# 03-PeripheralPart-V2_2.net
KiCad netlist of a schematic drawn in Altium Designer
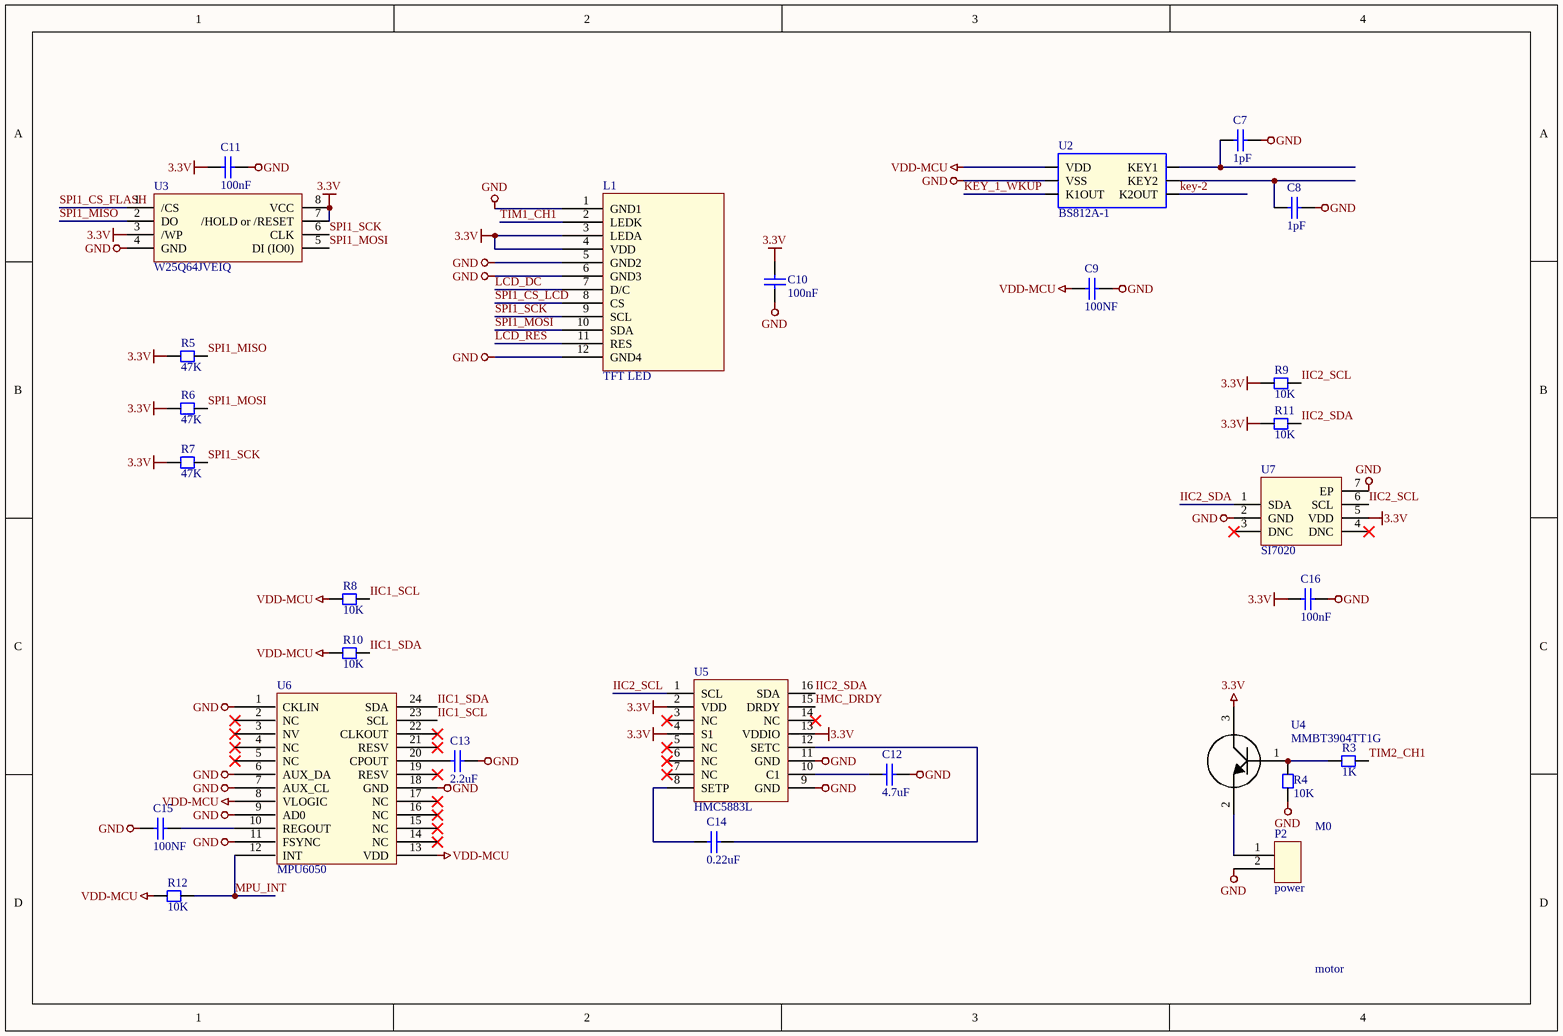
[diagram p0: 03-PeripheralPart-V2.2.SchDoc]

(export (version "E")
  (design (tool "Eeschema 10.0.6"))
  (components
    (comp (ref "C7")
      (value "1pF")
      (footprint "CC1005-0402")
      (description "贴片电容")
      (libsource (lib "tianxiaohua_Schlib") (part "Chip capacitor"))
    )
    (comp (ref "C8")
      (value "1pF")
      (footprint "CC1005-0402")
      (description "贴片电容")
      (libsource (lib "tianxiaohua_Schlib") (part "Chip capacitor"))
    )
    (comp (ref "C9")
      (value "100NF")
      (footprint "CC1005-0402")
      (description "贴片电容")
      (libsource (lib "tianxiaohua_Schlib") (part "Chip capacitor"))
    )
    (comp (ref "C10")
      (value "100nF")
      (footprint "CC1005-0402")
      (description "贴片电容")
      (libsource (lib "tianxiaohua_Schlib") (part "Chip capacitor"))
    )
    (comp (ref "C11")
      (value "100nF")
      (footprint "CC1005-0402")
      (description "贴片电容")
      (libsource (lib "tianxiaohua_Schlib") (part "Chip capacitor"))
    )
    (comp (ref "C12")
      (value "4.7uF")
      (footprint "CC1005-0402")
      (description "贴片电容")
      (libsource (lib "tianxiaohua_Schlib") (part "Chip capacitor"))
    )
    (comp (ref "C13")
      (value "2.2uF")
      (footprint "CC1005-0402")
      (description "贴片电容")
      (libsource (lib "tianxiaohua_Schlib") (part "Chip capacitor"))
    )
    (comp (ref "C14")
      (value "0.22uF")
      (footprint "CC1005-0402")
      (description "贴片电容")
      (libsource (lib "tianxiaohua_Schlib") (part "Chip capacitor"))
    )
    (comp (ref "C15")
      (value "100NF")
      (footprint "CC1005-0402")
      (description "贴片电容")
      (libsource (lib "tianxiaohua_Schlib") (part "Chip capacitor"))
    )
    (comp (ref "C16")
      (value "100nF")
      (footprint "CC1005-0402")
      (description "贴片电容")
      (libsource (lib "tianxiaohua_Schlib") (part "Chip capacitor"))
    )
    (comp (ref "L1")
      (value "TFT LED")
      (footprint "LCD-1.3-(2)")
      (description "1.3寸显示屏幕")
      (libsource (lib "tianxiaohua_Schlib") (part "LCD-IPSscreen-1.3"))
    )
    (comp (ref "M0")
      (value "motor")
      (footprint "motor")
      (description "震动马达")
      (libsource (lib "tianxiaohua_Schlib") (part "motor"))
    )
    (comp (ref "P2")
      (value "power")
      (footprint "POWER-3.7V")
      (libsource (lib "tianxiaohua_Schlib") (part "power"))
    )
    (comp (ref "R3")
      (value "1K")
      (footprint "CR1005-0402")
      (description "贴片电阻")
      (libsource (lib "tianxiaohua_Schlib") (part "Chip resistor"))
    )
    (comp (ref "R4")
      (value "10K")
      (footprint "CR1005-0402")
      (description "贴片电阻")
      (libsource (lib "") (part "Chip resistor_1"))
    )
    (comp (ref "R5")
      (value "47K")
      (footprint "CR1005-0402")
      (description "贴片电阻")
      (libsource (lib "tianxiaohua_Schlib") (part "Chip resistor"))
    )
    (comp (ref "R6")
      (value "47K")
      (footprint "CR1005-0402")
      (description "贴片电阻")
      (libsource (lib "tianxiaohua_Schlib") (part "Chip resistor"))
    )
    (comp (ref "R7")
      (value "47K")
      (footprint "CR1005-0402")
      (description "贴片电阻")
      (libsource (lib "tianxiaohua_Schlib") (part "Chip resistor"))
    )
    (comp (ref "R8")
      (value "10K")
      (footprint "CR1005-0402")
      (description "贴片电阻")
      (libsource (lib "tianxiaohua_Schlib") (part "Chip resistor"))
    )
    (comp (ref "R9")
      (value "10K")
      (footprint "CR1005-0402")
      (description "贴片电阻")
      (libsource (lib "tianxiaohua_Schlib") (part "Chip resistor"))
    )
    (comp (ref "R10")
      (value "10K")
      (footprint "CR1005-0402")
      (description "贴片电阻")
      (libsource (lib "tianxiaohua_Schlib") (part "Chip resistor"))
    )
    (comp (ref "R11")
      (value "10K")
      (footprint "CR1005-0402")
      (description "贴片电阻")
      (libsource (lib "tianxiaohua_Schlib") (part "Chip resistor"))
    )
    (comp (ref "R12")
      (value "10K")
      (footprint "CR1005-0402")
      (description "贴片电阻")
      (libsource (lib "tianxiaohua_Schlib") (part "Chip resistor"))
    )
    (comp (ref "U2")
      (value "BS812A-1")
      (footprint "SOT23-6")
      (description "触摸按键 两路 SOP23-6封装极简电路")
      (libsource (lib "tianxiaohua_Schlib") (part "BS812A-1"))
    )
    (comp (ref "U3")
      (value "W25Q64JVEIQ")
      (footprint "WSON-8_L8.0-W6.10-P1.27-TL-EP")
      (description "FLASH")
      (libsource (lib "tianxiaohua_Schlib") (part "W25Q256JVEIQ"))
    )
    (comp (ref "U4")
      (value "MMBT3904TT1G")
      (footprint "SOT-416")
      (description "NPN 电流 - 集电极（Ic）（最大值）：200mA 电压 - 集射极击穿（最大值）：40V SOT-23-3")
      (libsource (lib "tianxiaohua_Schlib") (part "MMBT3904TT1G"))
    )
    (comp (ref "U5")
      (value "HMC5883L")
      (footprint "LPCC-16_L3.0-W3.0-P0.50-BL")
      (description "三轴罗盘")
      (libsource (lib "tianxiaohua_Schlib") (part "HMC5883L"))
    )
    (comp (ref "U6")
      (value "MPU6050")
      (footprint "QFN24 - duplicate")
      (description "陀螺仪")
      (libsource (lib "tianxiaohua_Schlib") (part "MPU6050"))
    )
    (comp (ref "U7")
      (value "SI7020")
      (footprint "DFN-6")
      (description "温湿度传感器芯片")
      (libsource (lib "tianxiaohua_Schlib") (part "SI7020"))
    )
  )
  (nets
    (net (code "1") (name "/HMC_DRDY") (class "Default")
      (node (ref "U5") (pin "15") (pinfunction "DRDY_15") (pintype "passive"))
    )
    (net (code "2") (name "/IIC1_SCL") (class "Default")
      (node (ref "R8") (pin "1") (pinfunction "1_1") (pintype "passive"))
      (node (ref "U6") (pin "23") (pinfunction "SCL_23") (pintype "passive"))
    )
    (net (code "3") (name "/IIC1_SDA") (class "Default")
      (node (ref "R10") (pin "1") (pinfunction "1_1") (pintype "passive"))
      (node (ref "U6") (pin "24") (pinfunction "SDA_24") (pintype "passive"))
    )
    (net (code "4") (name "/IIC2_SCL") (class "Default")
      (node (ref "R9") (pin "1") (pinfunction "1_1") (pintype "passive"))
      (node (ref "U5") (pin "1") (pinfunction "SCL_1") (pintype "passive"))
      (node (ref "U7") (pin "6") (pinfunction "SCL_6") (pintype "passive"))
    )
    (net (code "5") (name "/IIC2_SDA") (class "Default")
      (node (ref "R11") (pin "1") (pinfunction "1_1") (pintype "passive"))
      (node (ref "U5") (pin "16") (pinfunction "SDA_16") (pintype "passive"))
      (node (ref "U7") (pin "1") (pinfunction "SDA_1") (pintype "passive"))
    )
    (net (code "6") (name "/KEY_1_WKUP") (class "Default")
      (node (ref "U2") (pin "3") (pinfunction "K1OUT_3") (pintype "passive"))
    )
    (net (code "7") (name "/LCD_DC") (class "Default")
      (node (ref "L1") (pin "7") (pinfunction "D/C_7") (pintype "passive"))
    )
    (net (code "8") (name "/LCD_RES") (class "Default")
      (node (ref "L1") (pin "11") (pinfunction "RES_11") (pintype "passive"))
    )
    (net (code "9") (name "/MPU_INT") (class "Default")
      (node (ref "R12") (pin "1") (pinfunction "1_1") (pintype "passive"))
      (node (ref "U6") (pin "12") (pinfunction "INT_12") (pintype "passive"))
    )
    (net (code "10") (name "/SPI1_CS_FLASH") (class "Default")
      (node (ref "U3") (pin "1") (pinfunction "/CS_1") (pintype "passive"))
    )
    (net (code "11") (name "/SPI1_CS_LCD") (class "Default")
      (node (ref "L1") (pin "8") (pinfunction "CS_8") (pintype "passive"))
    )
    (net (code "12") (name "/SPI1_MISO") (class "Default")
      (node (ref "R5") (pin "1") (pinfunction "1_1") (pintype "passive"))
      (node (ref "U3") (pin "2") (pinfunction "DO_2") (pintype "passive"))
    )
    (net (code "13") (name "/SPI1_MOSI") (class "Default")
      (node (ref "L1") (pin "10") (pinfunction "SDA_10") (pintype "passive"))
      (node (ref "R6") (pin "1") (pinfunction "1_1") (pintype "passive"))
      (node (ref "U3") (pin "5") (pinfunction "DI_(IO0)_5") (pintype "passive"))
    )
    (net (code "14") (name "/SPI1_SCK") (class "Default")
      (node (ref "L1") (pin "9") (pinfunction "SCL_9") (pintype "passive"))
      (node (ref "R7") (pin "1") (pinfunction "1_1") (pintype "passive"))
      (node (ref "U3") (pin "6") (pinfunction "CLK_6") (pintype "passive"))
    )
    (net (code "15") (name "/TIM1_CH1") (class "Default")
      (node (ref "L1") (pin "2") (pinfunction "LEDK_2") (pintype "passive"))
    )
    (net (code "16") (name "/TIM2_CH1") (class "Default")
      (node (ref "R3") (pin "1") (pinfunction "1_1") (pintype "passive"))
    )
    (net (code "17") (name "/key-2") (class "Default")
      (node (ref "U2") (pin "4") (pinfunction "K2OUT_4") (pintype "passive"))
    )
    (net (code "18") (name "3.3V") (class "Default")
      (node (ref "C10") (pin "1") (pinfunction "1_1") (pintype "passive"))
      (node (ref "C11") (pin "1") (pinfunction "1_1") (pintype "passive"))
      (node (ref "C16") (pin "1") (pinfunction "1_1") (pintype "passive"))
      (node (ref "L1") (pin "3") (pinfunction "LEDA_3") (pintype "passive"))
      (node (ref "L1") (pin "4") (pinfunction "VDD_4") (pintype "passive"))
      (node (ref "R11") (pin "2") (pinfunction "2_2") (pintype "passive"))
      (node (ref "R5") (pin "2") (pinfunction "2_2") (pintype "passive"))
      (node (ref "R6") (pin "2") (pinfunction "2_2") (pintype "passive"))
      (node (ref "R7") (pin "2") (pinfunction "2_2") (pintype "passive"))
      (node (ref "R9") (pin "2") (pinfunction "2_2") (pintype "passive"))
      (node (ref "U3") (pin "3") (pinfunction "/WP_3") (pintype "passive"))
      (node (ref "U3") (pin "7") (pinfunction "/HOLD_or_/RESET_7") (pintype "passive"))
      (node (ref "U3") (pin "8") (pinfunction "VCC_8") (pintype "passive"))
      (node (ref "U4") (pin "3") (pinfunction "3_3") (pintype "passive"))
      (node (ref "U5") (pin "13") (pinfunction "VDDIO_13") (pintype "passive"))
      (node (ref "U5") (pin "2") (pinfunction "VDD_2") (pintype "passive"))
      (node (ref "U5") (pin "4") (pinfunction "S1_4") (pintype "passive"))
      (node (ref "U7") (pin "5") (pinfunction "VDD_5") (pintype "passive"))
    )
    (net (code "19") (name "GND") (class "Default")
      (node (ref "C10") (pin "2") (pinfunction "2_2") (pintype "passive"))
      (node (ref "C11") (pin "2") (pinfunction "2_2") (pintype "passive"))
      (node (ref "C12") (pin "2") (pinfunction "2_2") (pintype "passive"))
      (node (ref "C13") (pin "2") (pinfunction "2_2") (pintype "passive"))
      (node (ref "C15") (pin "1") (pinfunction "1_1") (pintype "passive"))
      (node (ref "C16") (pin "2") (pinfunction "2_2") (pintype "passive"))
      (node (ref "C7") (pin "2") (pinfunction "2_2") (pintype "passive"))
      (node (ref "C8") (pin "2") (pinfunction "2_2") (pintype "passive"))
      (node (ref "C9") (pin "1") (pinfunction "1_1") (pintype "passive"))
      (node (ref "L1") (pin "1") (pinfunction "GND1_1") (pintype "passive"))
      (node (ref "L1") (pin "12") (pinfunction "GND4_12") (pintype "passive"))
      (node (ref "L1") (pin "5") (pinfunction "GND2_5") (pintype "passive"))
      (node (ref "L1") (pin "6") (pinfunction "GND3_6") (pintype "passive"))
      (node (ref "P2") (pin "2") (pinfunction "2_2") (pintype "passive"))
      (node (ref "R4") (pin "2") (pinfunction "2_2") (pintype "passive"))
      (node (ref "U2") (pin "2") (pinfunction "VSS_2") (pintype "passive"))
      (node (ref "U3") (pin "4") (pinfunction "GND_4") (pintype "passive"))
      (node (ref "U5") (pin "11") (pinfunction "GND_11") (pintype "passive"))
      (node (ref "U5") (pin "9") (pinfunction "GND_9") (pintype "passive"))
      (node (ref "U6") (pin "1") (pinfunction "CKLIN_1") (pintype "passive"))
      (node (ref "U6") (pin "11") (pinfunction "FSYNC_11") (pintype "passive"))
      (node (ref "U6") (pin "18") (pinfunction "GND_18") (pintype "passive"))
      (node (ref "U6") (pin "6") (pinfunction "AUX_DA_6") (pintype "passive"))
      (node (ref "U6") (pin "7") (pinfunction "AUX_CL_7") (pintype "passive"))
      (node (ref "U6") (pin "9") (pinfunction "AD0_9") (pintype "passive"))
      (node (ref "U7") (pin "2") (pinfunction "GND_2") (pintype "passive"))
      (node (ref "U7") (pin "7") (pinfunction "EP_7") (pintype "passive"))
    )
    (net (code "20") (name "Net-(P2-Pad1)") (class "Default")
      (node (ref "P2") (pin "1") (pinfunction "1_1") (pintype "passive"))
      (node (ref "U4") (pin "2") (pinfunction "2_2") (pintype "passive"))
    )
    (net (code "21") (name "Net-(R3-Pad2)") (class "Default")
      (node (ref "R3") (pin "2") (pinfunction "2_2") (pintype "passive"))
      (node (ref "R4") (pin "1") (pinfunction "1_1") (pintype "passive"))
      (node (ref "U4") (pin "1") (pinfunction "1_1") (pintype "passive"))
    )
    (net (code "22") (name "Net-(U2-KEY1)") (class "Default")
      (node (ref "C7") (pin "1") (pinfunction "1_1") (pintype "passive"))
      (node (ref "U2") (pin "6") (pinfunction "KEY1_6") (pintype "passive"))
    )
    (net (code "23") (name "Net-(U2-KEY2)") (class "Default")
      (node (ref "C8") (pin "1") (pinfunction "1_1") (pintype "passive"))
      (node (ref "U2") (pin "5") (pinfunction "KEY2_5") (pintype "passive"))
    )
    (net (code "24") (name "Net-(U5-C1)") (class "Default")
      (node (ref "C12") (pin "1") (pinfunction "1_1") (pintype "passive"))
      (node (ref "U5") (pin "10") (pinfunction "C1_10") (pintype "passive"))
    )
    (net (code "25") (name "Net-(U5-SETC)") (class "Default")
      (node (ref "C14") (pin "2") (pinfunction "2_2") (pintype "passive"))
      (node (ref "U5") (pin "12") (pinfunction "SETC_12") (pintype "passive"))
    )
    (net (code "26") (name "Net-(U5-SETP)") (class "Default")
      (node (ref "C14") (pin "1") (pinfunction "1_1") (pintype "passive"))
      (node (ref "U5") (pin "8") (pinfunction "SETP_8") (pintype "passive"))
    )
    (net (code "27") (name "Net-(U6-CPOUT)") (class "Default")
      (node (ref "C13") (pin "1") (pinfunction "1_1") (pintype "passive"))
      (node (ref "U6") (pin "20") (pinfunction "CPOUT_20") (pintype "passive"))
    )
    (net (code "28") (name "Net-(U6-REGOUT)") (class "Default")
      (node (ref "C15") (pin "2") (pinfunction "2_2") (pintype "passive"))
      (node (ref "U6") (pin "10") (pinfunction "REGOUT_10") (pintype "passive"))
    )
    (net (code "29") (name "VDD-MCU") (class "Default")
      (node (ref "C9") (pin "2") (pinfunction "2_2") (pintype "passive"))
      (node (ref "R10") (pin "2") (pinfunction "2_2") (pintype "passive"))
      (node (ref "R12") (pin "2") (pinfunction "2_2") (pintype "passive"))
      (node (ref "R8") (pin "2") (pinfunction "2_2") (pintype "passive"))
      (node (ref "U2") (pin "1") (pinfunction "VDD_1") (pintype "passive"))
      (node (ref "U6") (pin "13") (pinfunction "VDD_13") (pintype "passive"))
      (node (ref "U6") (pin "8") (pinfunction "VLOGIC_8") (pintype "passive"))
    )
    (net (code "30") (name "unconnected-(U5-NC-Pad3)") (class "Default")
      (node (ref "U5") (pin "3") (pinfunction "NC_3") (pintype "passive+no_connect"))
    )
    (net (code "31") (name "unconnected-(U5-NC-Pad5)") (class "Default")
      (node (ref "U5") (pin "5") (pinfunction "NC_5") (pintype "passive+no_connect"))
    )
    (net (code "32") (name "unconnected-(U5-NC-Pad6)") (class "Default")
      (node (ref "U5") (pin "6") (pinfunction "NC_6") (pintype "passive+no_connect"))
    )
    (net (code "33") (name "unconnected-(U5-NC-Pad7)") (class "Default")
      (node (ref "U5") (pin "7") (pinfunction "NC_7") (pintype "passive+no_connect"))
    )
    (net (code "34") (name "unconnected-(U5-NC-Pad14)") (class "Default")
      (node (ref "U5") (pin "14") (pinfunction "NC_14") (pintype "passive+no_connect"))
    )
    (net (code "35") (name "unconnected-(U6-CLKOUT-Pad22)") (class "Default")
      (node (ref "U6") (pin "22") (pinfunction "CLKOUT_22") (pintype "passive+no_connect"))
    )
    (net (code "36") (name "unconnected-(U6-NC-Pad2)") (class "Default")
      (node (ref "U6") (pin "2") (pinfunction "NC_2") (pintype "passive+no_connect"))
    )
    (net (code "37") (name "unconnected-(U6-NC-Pad4)") (class "Default")
      (node (ref "U6") (pin "4") (pinfunction "NC_4") (pintype "passive+no_connect"))
    )
    (net (code "38") (name "unconnected-(U6-NC-Pad5)") (class "Default")
      (node (ref "U6") (pin "5") (pinfunction "NC_5") (pintype "passive+no_connect"))
    )
    (net (code "39") (name "unconnected-(U6-NC-Pad14)") (class "Default")
      (node (ref "U6") (pin "14") (pinfunction "NC_14") (pintype "passive+no_connect"))
    )
    (net (code "40") (name "unconnected-(U6-NC-Pad15)") (class "Default")
      (node (ref "U6") (pin "15") (pinfunction "NC_15") (pintype "passive+no_connect"))
    )
    (net (code "41") (name "unconnected-(U6-NC-Pad16)") (class "Default")
      (node (ref "U6") (pin "16") (pinfunction "NC_16") (pintype "passive+no_connect"))
    )
    (net (code "42") (name "unconnected-(U6-NC-Pad17)") (class "Default")
      (node (ref "U6") (pin "17") (pinfunction "NC_17") (pintype "passive+no_connect"))
    )
    (net (code "43") (name "unconnected-(U6-NV-Pad3)") (class "Default")
      (node (ref "U6") (pin "3") (pinfunction "NV_3") (pintype "passive+no_connect"))
    )
    (net (code "44") (name "unconnected-(U6-RESV-Pad19)") (class "Default")
      (node (ref "U6") (pin "19") (pinfunction "RESV_19") (pintype "passive+no_connect"))
    )
    (net (code "45") (name "unconnected-(U6-RESV-Pad21)") (class "Default")
      (node (ref "U6") (pin "21") (pinfunction "RESV_21") (pintype "passive+no_connect"))
    )
    (net (code "46") (name "unconnected-(U7-DNC-Pad3)") (class "Default")
      (node (ref "U7") (pin "3") (pinfunction "DNC_3") (pintype "passive+no_connect"))
    )
    (net (code "47") (name "unconnected-(U7-DNC-Pad4)") (class "Default")
      (node (ref "U7") (pin "4") (pinfunction "DNC_4") (pintype "passive+no_connect"))
    )
  )
)
